# donut.net
KiCad netlist of a schematic drawn in EAGLE
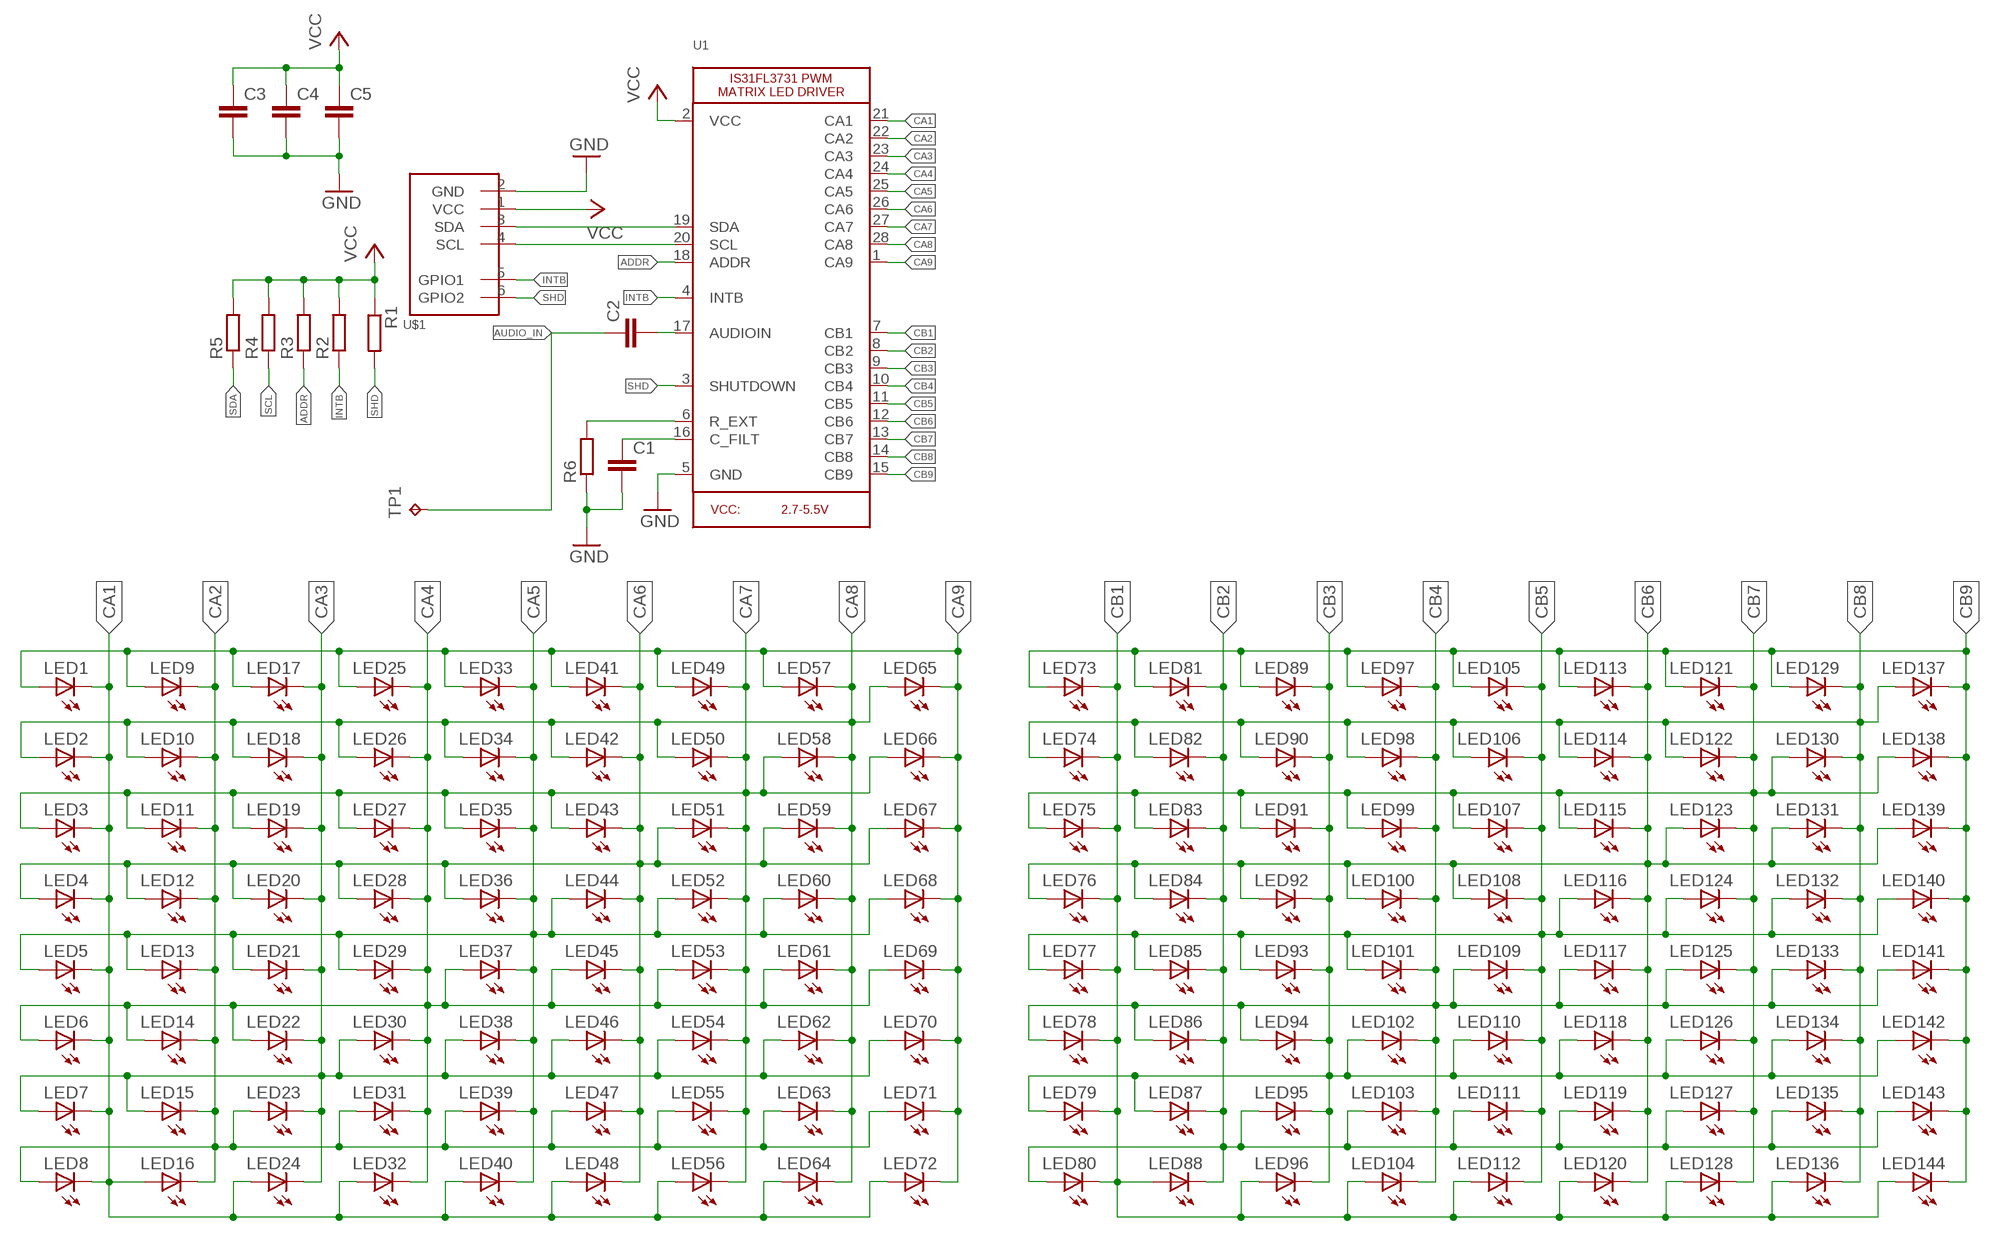
[diagram p0: schematic, sheet 1]

(export (version "E")
  (design (tool "Eeschema 10.0.6"))
  (components
    (comp (ref "C1")
      (value "C-EUC0603")
      (footprint "eagle-import:C0603")
      (libsource (lib "eagle-import") (part "C-EUC0603"))
    )
    (comp (ref "C2")
      (value "C-EUC0603")
      (footprint "eagle-import:C0603")
      (libsource (lib "eagle-import") (part "C-EUC0603"))
    )
    (comp (ref "C3")
      (value "C-EUC0603")
      (footprint "eagle-import:C0603")
      (libsource (lib "eagle-import") (part "C-EUC0603"))
    )
    (comp (ref "C4")
      (value "C-EUC0603")
      (footprint "eagle-import:C0603")
      (libsource (lib "eagle-import") (part "C-EUC0603"))
    )
    (comp (ref "C5")
      (value "C-EUC0603")
      (footprint "eagle-import:C0603")
      (libsource (lib "eagle-import") (part "C-EUC0603"))
    )
    (comp (ref "LED1")
      (value "LEDCHIP-LED0603")
      (footprint "eagle-import:CHIP-LED0603")
      (libsource (lib "eagle-import") (part "LEDCHIP-LED0603"))
    )
    (comp (ref "LED2")
      (value "LEDCHIP-LED0603")
      (footprint "eagle-import:CHIP-LED0603")
      (libsource (lib "eagle-import") (part "LEDCHIP-LED0603"))
    )
    (comp (ref "LED3")
      (value "LEDCHIP-LED0603")
      (footprint "eagle-import:CHIP-LED0603")
      (libsource (lib "eagle-import") (part "LEDCHIP-LED0603"))
    )
    (comp (ref "LED4")
      (value "LEDCHIP-LED0603")
      (footprint "eagle-import:CHIP-LED0603")
      (libsource (lib "eagle-import") (part "LEDCHIP-LED0603"))
    )
    (comp (ref "LED5")
      (value "LEDCHIP-LED0603")
      (footprint "eagle-import:CHIP-LED0603")
      (libsource (lib "eagle-import") (part "LEDCHIP-LED0603"))
    )
    (comp (ref "LED6")
      (value "LEDCHIP-LED0603")
      (footprint "eagle-import:CHIP-LED0603")
      (libsource (lib "eagle-import") (part "LEDCHIP-LED0603"))
    )
    (comp (ref "LED7")
      (value "LEDCHIP-LED0603")
      (footprint "eagle-import:CHIP-LED0603")
      (libsource (lib "eagle-import") (part "LEDCHIP-LED0603"))
    )
    (comp (ref "LED8")
      (value "LEDCHIP-LED0603")
      (footprint "eagle-import:CHIP-LED0603")
      (libsource (lib "eagle-import") (part "LEDCHIP-LED0603"))
    )
    (comp (ref "LED9")
      (value "LEDCHIP-LED0603")
      (footprint "eagle-import:CHIP-LED0603")
      (libsource (lib "eagle-import") (part "LEDCHIP-LED0603"))
    )
    (comp (ref "LED10")
      (value "LEDCHIP-LED0603")
      (footprint "eagle-import:CHIP-LED0603")
      (libsource (lib "eagle-import") (part "LEDCHIP-LED0603"))
    )
    (comp (ref "LED11")
      (value "LEDCHIP-LED0603")
      (footprint "eagle-import:CHIP-LED0603")
      (libsource (lib "eagle-import") (part "LEDCHIP-LED0603"))
    )
    (comp (ref "LED12")
      (value "LEDCHIP-LED0603")
      (footprint "eagle-import:CHIP-LED0603")
      (libsource (lib "eagle-import") (part "LEDCHIP-LED0603"))
    )
    (comp (ref "LED13")
      (value "LEDCHIP-LED0603")
      (footprint "eagle-import:CHIP-LED0603")
      (libsource (lib "eagle-import") (part "LEDCHIP-LED0603"))
    )
    (comp (ref "LED14")
      (value "LEDCHIP-LED0603")
      (footprint "eagle-import:CHIP-LED0603")
      (libsource (lib "eagle-import") (part "LEDCHIP-LED0603"))
    )
    (comp (ref "LED15")
      (value "LEDCHIP-LED0603")
      (footprint "eagle-import:CHIP-LED0603")
      (libsource (lib "eagle-import") (part "LEDCHIP-LED0603"))
    )
    (comp (ref "LED16")
      (value "LEDCHIP-LED0603")
      (footprint "eagle-import:CHIP-LED0603")
      (libsource (lib "eagle-import") (part "LEDCHIP-LED0603"))
    )
    (comp (ref "LED17")
      (value "LEDCHIP-LED0603")
      (footprint "eagle-import:CHIP-LED0603")
      (libsource (lib "eagle-import") (part "LEDCHIP-LED0603"))
    )
    (comp (ref "LED18")
      (value "LEDCHIP-LED0603")
      (footprint "eagle-import:CHIP-LED0603")
      (libsource (lib "eagle-import") (part "LEDCHIP-LED0603"))
    )
    (comp (ref "LED19")
      (value "LEDCHIP-LED0603")
      (footprint "eagle-import:CHIP-LED0603")
      (libsource (lib "eagle-import") (part "LEDCHIP-LED0603"))
    )
    (comp (ref "LED20")
      (value "LEDCHIP-LED0603")
      (footprint "eagle-import:CHIP-LED0603")
      (libsource (lib "eagle-import") (part "LEDCHIP-LED0603"))
    )
    (comp (ref "LED21")
      (value "LEDCHIP-LED0603")
      (footprint "eagle-import:CHIP-LED0603")
      (libsource (lib "eagle-import") (part "LEDCHIP-LED0603"))
    )
    (comp (ref "LED22")
      (value "LEDCHIP-LED0603")
      (footprint "eagle-import:CHIP-LED0603")
      (libsource (lib "eagle-import") (part "LEDCHIP-LED0603"))
    )
    (comp (ref "LED23")
      (value "LEDCHIP-LED0603")
      (footprint "eagle-import:CHIP-LED0603")
      (libsource (lib "eagle-import") (part "LEDCHIP-LED0603"))
    )
    (comp (ref "LED24")
      (value "LEDCHIP-LED0603")
      (footprint "eagle-import:CHIP-LED0603")
      (libsource (lib "eagle-import") (part "LEDCHIP-LED0603"))
    )
    (comp (ref "LED25")
      (value "LEDCHIP-LED0603")
      (footprint "eagle-import:CHIP-LED0603")
      (libsource (lib "eagle-import") (part "LEDCHIP-LED0603"))
    )
    (comp (ref "LED26")
      (value "LEDCHIP-LED0603")
      (footprint "eagle-import:CHIP-LED0603")
      (libsource (lib "eagle-import") (part "LEDCHIP-LED0603"))
    )
    (comp (ref "LED27")
      (value "LEDCHIP-LED0603")
      (footprint "eagle-import:CHIP-LED0603")
      (libsource (lib "eagle-import") (part "LEDCHIP-LED0603"))
    )
    (comp (ref "LED28")
      (value "LEDCHIP-LED0603")
      (footprint "eagle-import:CHIP-LED0603")
      (libsource (lib "eagle-import") (part "LEDCHIP-LED0603"))
    )
    (comp (ref "LED29")
      (value "LEDCHIP-LED0603")
      (footprint "eagle-import:CHIP-LED0603")
      (libsource (lib "eagle-import") (part "LEDCHIP-LED0603"))
    )
    (comp (ref "LED30")
      (value "LEDCHIP-LED0603")
      (footprint "eagle-import:CHIP-LED0603")
      (libsource (lib "eagle-import") (part "LEDCHIP-LED0603"))
    )
    (comp (ref "LED31")
      (value "LEDCHIP-LED0603")
      (footprint "eagle-import:CHIP-LED0603")
      (libsource (lib "eagle-import") (part "LEDCHIP-LED0603"))
    )
    (comp (ref "LED32")
      (value "LEDCHIP-LED0603")
      (footprint "eagle-import:CHIP-LED0603")
      (libsource (lib "eagle-import") (part "LEDCHIP-LED0603"))
    )
    (comp (ref "LED33")
      (value "LEDCHIP-LED0603")
      (footprint "eagle-import:CHIP-LED0603")
      (libsource (lib "eagle-import") (part "LEDCHIP-LED0603"))
    )
    (comp (ref "LED34")
      (value "LEDCHIP-LED0603")
      (footprint "eagle-import:CHIP-LED0603")
      (libsource (lib "eagle-import") (part "LEDCHIP-LED0603"))
    )
    (comp (ref "LED35")
      (value "LEDCHIP-LED0603")
      (footprint "eagle-import:CHIP-LED0603")
      (libsource (lib "eagle-import") (part "LEDCHIP-LED0603"))
    )
    (comp (ref "LED36")
      (value "LEDCHIP-LED0603")
      (footprint "eagle-import:CHIP-LED0603")
      (libsource (lib "eagle-import") (part "LEDCHIP-LED0603"))
    )
    (comp (ref "LED37")
      (value "LEDCHIP-LED0603")
      (footprint "eagle-import:CHIP-LED0603")
      (libsource (lib "eagle-import") (part "LEDCHIP-LED0603"))
    )
    (comp (ref "LED38")
      (value "LEDCHIP-LED0603")
      (footprint "eagle-import:CHIP-LED0603")
      (libsource (lib "eagle-import") (part "LEDCHIP-LED0603"))
    )
    (comp (ref "LED39")
      (value "LEDCHIP-LED0603")
      (footprint "eagle-import:CHIP-LED0603")
      (libsource (lib "eagle-import") (part "LEDCHIP-LED0603"))
    )
    (comp (ref "LED40")
      (value "LEDCHIP-LED0603")
      (footprint "eagle-import:CHIP-LED0603")
      (libsource (lib "eagle-import") (part "LEDCHIP-LED0603"))
    )
    (comp (ref "LED41")
      (value "LEDCHIP-LED0603")
      (footprint "eagle-import:CHIP-LED0603")
      (libsource (lib "eagle-import") (part "LEDCHIP-LED0603"))
    )
    (comp (ref "LED42")
      (value "LEDCHIP-LED0603")
      (footprint "eagle-import:CHIP-LED0603")
      (libsource (lib "eagle-import") (part "LEDCHIP-LED0603"))
    )
    (comp (ref "LED43")
      (value "LEDCHIP-LED0603")
      (footprint "eagle-import:CHIP-LED0603")
      (libsource (lib "eagle-import") (part "LEDCHIP-LED0603"))
    )
    (comp (ref "LED44")
      (value "LEDCHIP-LED0603")
      (footprint "eagle-import:CHIP-LED0603")
      (libsource (lib "eagle-import") (part "LEDCHIP-LED0603"))
    )
    (comp (ref "LED45")
      (value "LEDCHIP-LED0603")
      (footprint "eagle-import:CHIP-LED0603")
      (libsource (lib "eagle-import") (part "LEDCHIP-LED0603"))
    )
    (comp (ref "LED46")
      (value "LEDCHIP-LED0603")
      (footprint "eagle-import:CHIP-LED0603")
      (libsource (lib "eagle-import") (part "LEDCHIP-LED0603"))
    )
    (comp (ref "LED47")
      (value "LEDCHIP-LED0603")
      (footprint "eagle-import:CHIP-LED0603")
      (libsource (lib "eagle-import") (part "LEDCHIP-LED0603"))
    )
    (comp (ref "LED48")
      (value "LEDCHIP-LED0603")
      (footprint "eagle-import:CHIP-LED0603")
      (libsource (lib "eagle-import") (part "LEDCHIP-LED0603"))
    )
    (comp (ref "LED49")
      (value "LEDCHIP-LED0603")
      (footprint "eagle-import:CHIP-LED0603")
      (libsource (lib "eagle-import") (part "LEDCHIP-LED0603"))
    )
    (comp (ref "LED50")
      (value "LEDCHIP-LED0603")
      (footprint "eagle-import:CHIP-LED0603")
      (libsource (lib "eagle-import") (part "LEDCHIP-LED0603"))
    )
    (comp (ref "LED51")
      (value "LEDCHIP-LED0603")
      (footprint "eagle-import:CHIP-LED0603")
      (libsource (lib "eagle-import") (part "LEDCHIP-LED0603"))
    )
    (comp (ref "LED52")
      (value "LEDCHIP-LED0603")
      (footprint "eagle-import:CHIP-LED0603")
      (libsource (lib "eagle-import") (part "LEDCHIP-LED0603"))
    )
    (comp (ref "LED53")
      (value "LEDCHIP-LED0603")
      (footprint "eagle-import:CHIP-LED0603")
      (libsource (lib "eagle-import") (part "LEDCHIP-LED0603"))
    )
    (comp (ref "LED54")
      (value "LEDCHIP-LED0603")
      (footprint "eagle-import:CHIP-LED0603")
      (libsource (lib "eagle-import") (part "LEDCHIP-LED0603"))
    )
    (comp (ref "LED55")
      (value "LEDCHIP-LED0603")
      (footprint "eagle-import:CHIP-LED0603")
      (libsource (lib "eagle-import") (part "LEDCHIP-LED0603"))
    )
    (comp (ref "LED56")
      (value "LEDCHIP-LED0603")
      (footprint "eagle-import:CHIP-LED0603")
      (libsource (lib "eagle-import") (part "LEDCHIP-LED0603"))
    )
    (comp (ref "LED57")
      (value "LEDCHIP-LED0603")
      (footprint "eagle-import:CHIP-LED0603")
      (libsource (lib "eagle-import") (part "LEDCHIP-LED0603"))
    )
    (comp (ref "LED58")
      (value "LEDCHIP-LED0603")
      (footprint "eagle-import:CHIP-LED0603")
      (libsource (lib "eagle-import") (part "LEDCHIP-LED0603"))
    )
    (comp (ref "LED59")
      (value "LEDCHIP-LED0603")
      (footprint "eagle-import:CHIP-LED0603")
      (libsource (lib "eagle-import") (part "LEDCHIP-LED0603"))
    )
    (comp (ref "LED60")
      (value "LEDCHIP-LED0603")
      (footprint "eagle-import:CHIP-LED0603")
      (libsource (lib "eagle-import") (part "LEDCHIP-LED0603"))
    )
    (comp (ref "LED61")
      (value "LEDCHIP-LED0603")
      (footprint "eagle-import:CHIP-LED0603")
      (libsource (lib "eagle-import") (part "LEDCHIP-LED0603"))
    )
    (comp (ref "LED62")
      (value "LEDCHIP-LED0603")
      (footprint "eagle-import:CHIP-LED0603")
      (libsource (lib "eagle-import") (part "LEDCHIP-LED0603"))
    )
    (comp (ref "LED63")
      (value "LEDCHIP-LED0603")
      (footprint "eagle-import:CHIP-LED0603")
      (libsource (lib "eagle-import") (part "LEDCHIP-LED0603"))
    )
    (comp (ref "LED64")
      (value "LEDCHIP-LED0603")
      (footprint "eagle-import:CHIP-LED0603")
      (libsource (lib "eagle-import") (part "LEDCHIP-LED0603"))
    )
    (comp (ref "LED65")
      (value "LEDCHIP-LED0603")
      (footprint "eagle-import:CHIP-LED0603")
      (libsource (lib "eagle-import") (part "LEDCHIP-LED0603"))
    )
    (comp (ref "LED66")
      (value "LEDCHIP-LED0603")
      (footprint "eagle-import:CHIP-LED0603")
      (libsource (lib "eagle-import") (part "LEDCHIP-LED0603"))
    )
    (comp (ref "LED67")
      (value "LEDCHIP-LED0603")
      (footprint "eagle-import:CHIP-LED0603")
      (libsource (lib "eagle-import") (part "LEDCHIP-LED0603"))
    )
    (comp (ref "LED68")
      (value "LEDCHIP-LED0603")
      (footprint "eagle-import:CHIP-LED0603")
      (libsource (lib "eagle-import") (part "LEDCHIP-LED0603"))
    )
    (comp (ref "LED69")
      (value "LEDCHIP-LED0603")
      (footprint "eagle-import:CHIP-LED0603")
      (libsource (lib "eagle-import") (part "LEDCHIP-LED0603"))
    )
    (comp (ref "LED70")
      (value "LEDCHIP-LED0603")
      (footprint "eagle-import:CHIP-LED0603")
      (libsource (lib "eagle-import") (part "LEDCHIP-LED0603"))
    )
    (comp (ref "LED71")
      (value "LEDCHIP-LED0603")
      (footprint "eagle-import:CHIP-LED0603")
      (libsource (lib "eagle-import") (part "LEDCHIP-LED0603"))
    )
    (comp (ref "LED72")
      (value "LEDCHIP-LED0603")
      (footprint "eagle-import:CHIP-LED0603")
      (libsource (lib "eagle-import") (part "LEDCHIP-LED0603"))
    )
    (comp (ref "LED73")
      (value "LEDCHIP-LED0603")
      (footprint "eagle-import:CHIP-LED0603")
      (libsource (lib "eagle-import") (part "LEDCHIP-LED0603"))
    )
    (comp (ref "LED74")
      (value "LEDCHIP-LED0603")
      (footprint "eagle-import:CHIP-LED0603")
      (libsource (lib "eagle-import") (part "LEDCHIP-LED0603"))
    )
    (comp (ref "LED75")
      (value "LEDCHIP-LED0603")
      (footprint "eagle-import:CHIP-LED0603")
      (libsource (lib "eagle-import") (part "LEDCHIP-LED0603"))
    )
    (comp (ref "LED76")
      (value "LEDCHIP-LED0603")
      (footprint "eagle-import:CHIP-LED0603")
      (libsource (lib "eagle-import") (part "LEDCHIP-LED0603"))
    )
    (comp (ref "LED77")
      (value "LEDCHIP-LED0603")
      (footprint "eagle-import:CHIP-LED0603")
      (libsource (lib "eagle-import") (part "LEDCHIP-LED0603"))
    )
    (comp (ref "LED78")
      (value "LEDCHIP-LED0603")
      (footprint "eagle-import:CHIP-LED0603")
      (libsource (lib "eagle-import") (part "LEDCHIP-LED0603"))
    )
    (comp (ref "LED79")
      (value "LEDCHIP-LED0603")
      (footprint "eagle-import:CHIP-LED0603")
      (libsource (lib "eagle-import") (part "LEDCHIP-LED0603"))
    )
    (comp (ref "LED80")
      (value "LEDCHIP-LED0603")
      (footprint "eagle-import:CHIP-LED0603")
      (libsource (lib "eagle-import") (part "LEDCHIP-LED0603"))
    )
    (comp (ref "LED81")
      (value "LEDCHIP-LED0603")
      (footprint "eagle-import:CHIP-LED0603")
      (libsource (lib "eagle-import") (part "LEDCHIP-LED0603"))
    )
    (comp (ref "LED82")
      (value "LEDCHIP-LED0603")
      (footprint "eagle-import:CHIP-LED0603")
      (libsource (lib "eagle-import") (part "LEDCHIP-LED0603"))
    )
    (comp (ref "LED83")
      (value "LEDCHIP-LED0603")
      (footprint "eagle-import:CHIP-LED0603")
      (libsource (lib "eagle-import") (part "LEDCHIP-LED0603"))
    )
    (comp (ref "LED84")
      (value "LEDCHIP-LED0603")
      (footprint "eagle-import:CHIP-LED0603")
      (libsource (lib "eagle-import") (part "LEDCHIP-LED0603"))
    )
    (comp (ref "LED85")
      (value "LEDCHIP-LED0603")
      (footprint "eagle-import:CHIP-LED0603")
      (libsource (lib "eagle-import") (part "LEDCHIP-LED0603"))
    )
    (comp (ref "LED86")
      (value "LEDCHIP-LED0603")
      (footprint "eagle-import:CHIP-LED0603")
      (libsource (lib "eagle-import") (part "LEDCHIP-LED0603"))
    )
    (comp (ref "LED87")
      (value "LEDCHIP-LED0603")
      (footprint "eagle-import:CHIP-LED0603")
      (libsource (lib "eagle-import") (part "LEDCHIP-LED0603"))
    )
    (comp (ref "LED88")
      (value "LEDCHIP-LED0603")
      (footprint "eagle-import:CHIP-LED0603")
      (libsource (lib "eagle-import") (part "LEDCHIP-LED0603"))
    )
    (comp (ref "LED89")
      (value "LEDCHIP-LED0603")
      (footprint "eagle-import:CHIP-LED0603")
      (libsource (lib "eagle-import") (part "LEDCHIP-LED0603"))
    )
    (comp (ref "LED90")
      (value "LEDCHIP-LED0603")
      (footprint "eagle-import:CHIP-LED0603")
      (libsource (lib "eagle-import") (part "LEDCHIP-LED0603"))
    )
    (comp (ref "LED91")
      (value "LEDCHIP-LED0603")
      (footprint "eagle-import:CHIP-LED0603")
      (libsource (lib "eagle-import") (part "LEDCHIP-LED0603"))
    )
    (comp (ref "LED92")
      (value "LEDCHIP-LED0603")
      (footprint "eagle-import:CHIP-LED0603")
      (libsource (lib "eagle-import") (part "LEDCHIP-LED0603"))
    )
    (comp (ref "LED93")
      (value "LEDCHIP-LED0603")
      (footprint "eagle-import:CHIP-LED0603")
      (libsource (lib "eagle-import") (part "LEDCHIP-LED0603"))
    )
    (comp (ref "LED94")
      (value "LEDCHIP-LED0603")
      (footprint "eagle-import:CHIP-LED0603")
      (libsource (lib "eagle-import") (part "LEDCHIP-LED0603"))
    )
    (comp (ref "LED95")
      (value "LEDCHIP-LED0603")
      (footprint "eagle-import:CHIP-LED0603")
      (libsource (lib "eagle-import") (part "LEDCHIP-LED0603"))
    )
    (comp (ref "LED96")
      (value "LEDCHIP-LED0603")
      (footprint "eagle-import:CHIP-LED0603")
      (libsource (lib "eagle-import") (part "LEDCHIP-LED0603"))
    )
    (comp (ref "LED97")
      (value "LEDCHIP-LED0603")
      (footprint "eagle-import:CHIP-LED0603")
      (libsource (lib "eagle-import") (part "LEDCHIP-LED0603"))
    )
    (comp (ref "LED98")
      (value "LEDCHIP-LED0603")
      (footprint "eagle-import:CHIP-LED0603")
      (libsource (lib "eagle-import") (part "LEDCHIP-LED0603"))
    )
    (comp (ref "LED99")
      (value "LEDCHIP-LED0603")
      (footprint "eagle-import:CHIP-LED0603")
      (libsource (lib "eagle-import") (part "LEDCHIP-LED0603"))
    )
    (comp (ref "LED100")
      (value "LEDCHIP-LED0603")
      (footprint "eagle-import:CHIP-LED0603")
      (libsource (lib "eagle-import") (part "LEDCHIP-LED0603"))
    )
    (comp (ref "LED101")
      (value "LEDCHIP-LED0603")
      (footprint "eagle-import:CHIP-LED0603")
      (libsource (lib "eagle-import") (part "LEDCHIP-LED0603"))
    )
    (comp (ref "LED102")
      (value "LEDCHIP-LED0603")
      (footprint "eagle-import:CHIP-LED0603")
      (libsource (lib "eagle-import") (part "LEDCHIP-LED0603"))
    )
    (comp (ref "LED103")
      (value "LEDCHIP-LED0603")
      (footprint "eagle-import:CHIP-LED0603")
      (libsource (lib "eagle-import") (part "LEDCHIP-LED0603"))
    )
    (comp (ref "LED104")
      (value "LEDCHIP-LED0603")
      (footprint "eagle-import:CHIP-LED0603")
      (libsource (lib "eagle-import") (part "LEDCHIP-LED0603"))
    )
    (comp (ref "LED105")
      (value "LEDCHIP-LED0603")
      (footprint "eagle-import:CHIP-LED0603")
      (libsource (lib "eagle-import") (part "LEDCHIP-LED0603"))
    )
    (comp (ref "LED106")
      (value "LEDCHIP-LED0603")
      (footprint "eagle-import:CHIP-LED0603")
      (libsource (lib "eagle-import") (part "LEDCHIP-LED0603"))
    )
    (comp (ref "LED107")
      (value "LEDCHIP-LED0603")
      (footprint "eagle-import:CHIP-LED0603")
      (libsource (lib "eagle-import") (part "LEDCHIP-LED0603"))
    )
    (comp (ref "LED108")
      (value "LEDCHIP-LED0603")
      (footprint "eagle-import:CHIP-LED0603")
      (libsource (lib "eagle-import") (part "LEDCHIP-LED0603"))
    )
    (comp (ref "LED109")
      (value "LEDCHIP-LED0603")
      (footprint "eagle-import:CHIP-LED0603")
      (libsource (lib "eagle-import") (part "LEDCHIP-LED0603"))
    )
    (comp (ref "LED110")
      (value "LEDCHIP-LED0603")
      (footprint "eagle-import:CHIP-LED0603")
      (libsource (lib "eagle-import") (part "LEDCHIP-LED0603"))
    )
    (comp (ref "LED111")
      (value "LEDCHIP-LED0603")
      (footprint "eagle-import:CHIP-LED0603")
      (libsource (lib "eagle-import") (part "LEDCHIP-LED0603"))
    )
    (comp (ref "LED112")
      (value "LEDCHIP-LED0603")
      (footprint "eagle-import:CHIP-LED0603")
      (libsource (lib "eagle-import") (part "LEDCHIP-LED0603"))
    )
    (comp (ref "LED113")
      (value "LEDCHIP-LED0603")
      (footprint "eagle-import:CHIP-LED0603")
      (libsource (lib "eagle-import") (part "LEDCHIP-LED0603"))
    )
    (comp (ref "LED114")
      (value "LEDCHIP-LED0603")
      (footprint "eagle-import:CHIP-LED0603")
      (libsource (lib "eagle-import") (part "LEDCHIP-LED0603"))
    )
    (comp (ref "LED115")
      (value "LEDCHIP-LED0603")
      (footprint "eagle-import:CHIP-LED0603")
      (libsource (lib "eagle-import") (part "LEDCHIP-LED0603"))
    )
    (comp (ref "LED116")
      (value "LEDCHIP-LED0603")
      (footprint "eagle-import:CHIP-LED0603")
      (libsource (lib "eagle-import") (part "LEDCHIP-LED0603"))
    )
    (comp (ref "LED117")
      (value "LEDCHIP-LED0603")
      (footprint "eagle-import:CHIP-LED0603")
      (libsource (lib "eagle-import") (part "LEDCHIP-LED0603"))
    )
    (comp (ref "LED118")
      (value "LEDCHIP-LED0603")
      (footprint "eagle-import:CHIP-LED0603")
      (libsource (lib "eagle-import") (part "LEDCHIP-LED0603"))
    )
    (comp (ref "LED119")
      (value "LEDCHIP-LED0603")
      (footprint "eagle-import:CHIP-LED0603")
      (libsource (lib "eagle-import") (part "LEDCHIP-LED0603"))
    )
    (comp (ref "LED120")
      (value "LEDCHIP-LED0603")
      (footprint "eagle-import:CHIP-LED0603")
      (libsource (lib "eagle-import") (part "LEDCHIP-LED0603"))
    )
    (comp (ref "LED121")
      (value "LEDCHIP-LED0603")
      (footprint "eagle-import:CHIP-LED0603")
      (libsource (lib "eagle-import") (part "LEDCHIP-LED0603"))
    )
    (comp (ref "LED122")
      (value "LEDCHIP-LED0603")
      (footprint "eagle-import:CHIP-LED0603")
      (libsource (lib "eagle-import") (part "LEDCHIP-LED0603"))
    )
    (comp (ref "LED123")
      (value "LEDCHIP-LED0603")
      (footprint "eagle-import:CHIP-LED0603")
      (libsource (lib "eagle-import") (part "LEDCHIP-LED0603"))
    )
    (comp (ref "LED124")
      (value "LEDCHIP-LED0603")
      (footprint "eagle-import:CHIP-LED0603")
      (libsource (lib "eagle-import") (part "LEDCHIP-LED0603"))
    )
    (comp (ref "LED125")
      (value "LEDCHIP-LED0603")
      (footprint "eagle-import:CHIP-LED0603")
      (libsource (lib "eagle-import") (part "LEDCHIP-LED0603"))
    )
    (comp (ref "LED126")
      (value "LEDCHIP-LED0603")
      (footprint "eagle-import:CHIP-LED0603")
      (libsource (lib "eagle-import") (part "LEDCHIP-LED0603"))
    )
    (comp (ref "LED127")
      (value "LEDCHIP-LED0603")
      (footprint "eagle-import:CHIP-LED0603")
      (libsource (lib "eagle-import") (part "LEDCHIP-LED0603"))
    )
    (comp (ref "LED128")
      (value "LEDCHIP-LED0603")
      (footprint "eagle-import:CHIP-LED0603")
      (libsource (lib "eagle-import") (part "LEDCHIP-LED0603"))
    )
    (comp (ref "LED129")
      (value "LEDCHIP-LED0603")
      (footprint "eagle-import:CHIP-LED0603")
      (libsource (lib "eagle-import") (part "LEDCHIP-LED0603"))
    )
    (comp (ref "LED130")
      (value "LEDCHIP-LED0603")
      (footprint "eagle-import:CHIP-LED0603")
      (libsource (lib "eagle-import") (part "LEDCHIP-LED0603"))
    )
    (comp (ref "LED131")
      (value "LEDCHIP-LED0603")
      (footprint "eagle-import:CHIP-LED0603")
      (libsource (lib "eagle-import") (part "LEDCHIP-LED0603"))
    )
    (comp (ref "LED132")
      (value "LEDCHIP-LED0603")
      (footprint "eagle-import:CHIP-LED0603")
      (libsource (lib "eagle-import") (part "LEDCHIP-LED0603"))
    )
    (comp (ref "LED133")
      (value "LEDCHIP-LED0603")
      (footprint "eagle-import:CHIP-LED0603")
      (libsource (lib "eagle-import") (part "LEDCHIP-LED0603"))
    )
    (comp (ref "LED134")
      (value "LEDCHIP-LED0603")
      (footprint "eagle-import:CHIP-LED0603")
      (libsource (lib "eagle-import") (part "LEDCHIP-LED0603"))
    )
    (comp (ref "LED135")
      (value "LEDCHIP-LED0603")
      (footprint "eagle-import:CHIP-LED0603")
      (libsource (lib "eagle-import") (part "LEDCHIP-LED0603"))
    )
    (comp (ref "LED136")
      (value "LEDCHIP-LED0603")
      (footprint "eagle-import:CHIP-LED0603")
      (libsource (lib "eagle-import") (part "LEDCHIP-LED0603"))
    )
    (comp (ref "LED137")
      (value "LEDCHIP-LED0603")
      (footprint "eagle-import:CHIP-LED0603")
      (libsource (lib "eagle-import") (part "LEDCHIP-LED0603"))
    )
    (comp (ref "LED138")
      (value "LEDCHIP-LED0603")
      (footprint "eagle-import:CHIP-LED0603")
      (libsource (lib "eagle-import") (part "LEDCHIP-LED0603"))
    )
    (comp (ref "LED139")
      (value "LEDCHIP-LED0603")
      (footprint "eagle-import:CHIP-LED0603")
      (libsource (lib "eagle-import") (part "LEDCHIP-LED0603"))
    )
    (comp (ref "LED140")
      (value "LEDCHIP-LED0603")
      (footprint "eagle-import:CHIP-LED0603")
      (libsource (lib "eagle-import") (part "LEDCHIP-LED0603"))
    )
    (comp (ref "LED141")
      (value "LEDCHIP-LED0603")
      (footprint "eagle-import:CHIP-LED0603")
      (libsource (lib "eagle-import") (part "LEDCHIP-LED0603"))
    )
    (comp (ref "LED142")
      (value "LEDCHIP-LED0603")
      (footprint "eagle-import:CHIP-LED0603")
      (libsource (lib "eagle-import") (part "LEDCHIP-LED0603"))
    )
    (comp (ref "LED143")
      (value "LEDCHIP-LED0603")
      (footprint "eagle-import:CHIP-LED0603")
      (libsource (lib "eagle-import") (part "LEDCHIP-LED0603"))
    )
    (comp (ref "LED144")
      (value "LEDCHIP-LED0603")
      (footprint "eagle-import:CHIP-LED0603")
      (libsource (lib "eagle-import") (part "LEDCHIP-LED0603"))
    )
    (comp (ref "R1")
      (value "R-EU_R0603")
      (footprint "eagle-import:R0603")
      (libsource (lib "eagle-import") (part "R-EU_R0603"))
    )
    (comp (ref "R2")
      (value "R-EU_R0603")
      (footprint "eagle-import:R0603")
      (libsource (lib "eagle-import") (part "R-EU_R0603"))
    )
    (comp (ref "R3")
      (value "R-EU_R0603")
      (footprint "eagle-import:R0603")
      (libsource (lib "eagle-import") (part "R-EU_R0603"))
    )
    (comp (ref "R4")
      (value "R-EU_R0603")
      (footprint "eagle-import:R0603")
      (libsource (lib "eagle-import") (part "R-EU_R0603"))
    )
    (comp (ref "R5")
      (value "R-EU_R0603")
      (footprint "eagle-import:R0603")
      (libsource (lib "eagle-import") (part "R-EU_R0603"))
    )
    (comp (ref "R6")
      (value "R-EU_R0603")
      (footprint "eagle-import:R0603")
      (libsource (lib "eagle-import") (part "R-EU_R0603"))
    )
    (comp (ref "TP1")
      (value "TPB1,27")
      (footprint "eagle-import:B1,27")
      (libsource (lib "eagle-import") (part "TPB1,27"))
    )
    (comp (ref "U$1")
      (value "SAO-SHITTY-ADDONBADGE")
      (footprint "eagle-import:2X3-SHROUDED")
      (libsource (lib "eagle-import") (part "SAO-SHITTY-ADDONBADGE"))
    )
    (comp (ref "U1")
      (value "IS31FL3731SSOP")
      (footprint "eagle-import:SSOP28DB")
      (libsource (lib "eagle-import") (part "IS31FL3731SSOP"))
    )
  )
  (nets
    (net (code "1") (name "ADDR") (class "Default")
      (node (ref "R3") (pin "1") (pinfunction "1_1") (pintype "passive"))
      (node (ref "U1") (pin "18") (pinfunction "ADDR_18") (pintype "bidirectional"))
    )
    (net (code "2") (name "AUDIO_IN") (class "Default")
      (node (ref "C2") (pin "1") (pinfunction "1_1") (pintype "passive"))
      (node (ref "TP1") (pin "TP") (pinfunction "TP_TP") (pintype "input"))
    )
    (net (code "3") (name "CA1") (class "Default")
      (node (ref "LED1") (pin "C") (pinfunction "C_C") (pintype "passive"))
      (node (ref "LED16") (pin "A") (pinfunction "A_A") (pintype "passive"))
      (node (ref "LED2") (pin "C") (pinfunction "C_C") (pintype "passive"))
      (node (ref "LED24") (pin "A") (pinfunction "A_A") (pintype "passive"))
      (node (ref "LED3") (pin "C") (pinfunction "C_C") (pintype "passive"))
      (node (ref "LED32") (pin "A") (pinfunction "A_A") (pintype "passive"))
      (node (ref "LED4") (pin "C") (pinfunction "C_C") (pintype "passive"))
      (node (ref "LED40") (pin "A") (pinfunction "A_A") (pintype "passive"))
      (node (ref "LED48") (pin "A") (pinfunction "A_A") (pintype "passive"))
      (node (ref "LED5") (pin "C") (pinfunction "C_C") (pintype "passive"))
      (node (ref "LED56") (pin "A") (pinfunction "A_A") (pintype "passive"))
      (node (ref "LED6") (pin "C") (pinfunction "C_C") (pintype "passive"))
      (node (ref "LED64") (pin "A") (pinfunction "A_A") (pintype "passive"))
      (node (ref "LED7") (pin "C") (pinfunction "C_C") (pintype "passive"))
      (node (ref "LED72") (pin "A") (pinfunction "A_A") (pintype "passive"))
      (node (ref "LED8") (pin "C") (pinfunction "C_C") (pintype "passive"))
      (node (ref "U1") (pin "21") (pinfunction "CA1_21") (pintype "bidirectional"))
    )
    (net (code "4") (name "CA2") (class "Default")
      (node (ref "LED10") (pin "C") (pinfunction "C_C") (pintype "passive"))
      (node (ref "LED11") (pin "C") (pinfunction "C_C") (pintype "passive"))
      (node (ref "LED12") (pin "C") (pinfunction "C_C") (pintype "passive"))
      (node (ref "LED13") (pin "C") (pinfunction "C_C") (pintype "passive"))
      (node (ref "LED14") (pin "C") (pinfunction "C_C") (pintype "passive"))
      (node (ref "LED15") (pin "C") (pinfunction "C_C") (pintype "passive"))
      (node (ref "LED16") (pin "C") (pinfunction "C_C") (pintype "passive"))
      (node (ref "LED23") (pin "A") (pinfunction "A_A") (pintype "passive"))
      (node (ref "LED31") (pin "A") (pinfunction "A_A") (pintype "passive"))
      (node (ref "LED39") (pin "A") (pinfunction "A_A") (pintype "passive"))
      (node (ref "LED47") (pin "A") (pinfunction "A_A") (pintype "passive"))
      (node (ref "LED55") (pin "A") (pinfunction "A_A") (pintype "passive"))
      (node (ref "LED63") (pin "A") (pinfunction "A_A") (pintype "passive"))
      (node (ref "LED71") (pin "A") (pinfunction "A_A") (pintype "passive"))
      (node (ref "LED8") (pin "A") (pinfunction "A_A") (pintype "passive"))
      (node (ref "LED9") (pin "C") (pinfunction "C_C") (pintype "passive"))
      (node (ref "U1") (pin "22") (pinfunction "CA2_22") (pintype "bidirectional"))
    )
    (net (code "5") (name "CA3") (class "Default")
      (node (ref "LED15") (pin "A") (pinfunction "A_A") (pintype "passive"))
      (node (ref "LED17") (pin "C") (pinfunction "C_C") (pintype "passive"))
      (node (ref "LED18") (pin "C") (pinfunction "C_C") (pintype "passive"))
      (node (ref "LED19") (pin "C") (pinfunction "C_C") (pintype "passive"))
      (node (ref "LED20") (pin "C") (pinfunction "C_C") (pintype "passive"))
      (node (ref "LED21") (pin "C") (pinfunction "C_C") (pintype "passive"))
      (node (ref "LED22") (pin "C") (pinfunction "C_C") (pintype "passive"))
      (node (ref "LED23") (pin "C") (pinfunction "C_C") (pintype "passive"))
      (node (ref "LED24") (pin "C") (pinfunction "C_C") (pintype "passive"))
      (node (ref "LED30") (pin "A") (pinfunction "A_A") (pintype "passive"))
      (node (ref "LED38") (pin "A") (pinfunction "A_A") (pintype "passive"))
      (node (ref "LED46") (pin "A") (pinfunction "A_A") (pintype "passive"))
      (node (ref "LED54") (pin "A") (pinfunction "A_A") (pintype "passive"))
      (node (ref "LED62") (pin "A") (pinfunction "A_A") (pintype "passive"))
      (node (ref "LED7") (pin "A") (pinfunction "A_A") (pintype "passive"))
      (node (ref "LED70") (pin "A") (pinfunction "A_A") (pintype "passive"))
      (node (ref "U1") (pin "23") (pinfunction "CA3_23") (pintype "bidirectional"))
    )
    (net (code "6") (name "CA4") (class "Default")
      (node (ref "LED14") (pin "A") (pinfunction "A_A") (pintype "passive"))
      (node (ref "LED22") (pin "A") (pinfunction "A_A") (pintype "passive"))
      (node (ref "LED25") (pin "C") (pinfunction "C_C") (pintype "passive"))
      (node (ref "LED26") (pin "C") (pinfunction "C_C") (pintype "passive"))
      (node (ref "LED27") (pin "C") (pinfunction "C_C") (pintype "passive"))
      (node (ref "LED28") (pin "C") (pinfunction "C_C") (pintype "passive"))
      (node (ref "LED29") (pin "C") (pinfunction "C_C") (pintype "passive"))
      (node (ref "LED30") (pin "C") (pinfunction "C_C") (pintype "passive"))
      (node (ref "LED31") (pin "C") (pinfunction "C_C") (pintype "passive"))
      (node (ref "LED32") (pin "C") (pinfunction "C_C") (pintype "passive"))
      (node (ref "LED37") (pin "A") (pinfunction "A_A") (pintype "passive"))
      (node (ref "LED45") (pin "A") (pinfunction "A_A") (pintype "passive"))
      (node (ref "LED53") (pin "A") (pinfunction "A_A") (pintype "passive"))
      (node (ref "LED6") (pin "A") (pinfunction "A_A") (pintype "passive"))
      (node (ref "LED61") (pin "A") (pinfunction "A_A") (pintype "passive"))
      (node (ref "LED69") (pin "A") (pinfunction "A_A") (pintype "passive"))
      (node (ref "U1") (pin "24") (pinfunction "CA4_24") (pintype "bidirectional"))
    )
    (net (code "7") (name "CA5") (class "Default")
      (node (ref "LED13") (pin "A") (pinfunction "A_A") (pintype "passive"))
      (node (ref "LED21") (pin "A") (pinfunction "A_A") (pintype "passive"))
      (node (ref "LED29") (pin "A") (pinfunction "A_A") (pintype "passive"))
      (node (ref "LED33") (pin "C") (pinfunction "C_C") (pintype "passive"))
      (node (ref "LED34") (pin "C") (pinfunction "C_C") (pintype "passive"))
      (node (ref "LED35") (pin "C") (pinfunction "C_C") (pintype "passive"))
      (node (ref "LED36") (pin "C") (pinfunction "C_C") (pintype "passive"))
      (node (ref "LED37") (pin "C") (pinfunction "C_C") (pintype "passive"))
      (node (ref "LED38") (pin "C") (pinfunction "C_C") (pintype "passive"))
      (node (ref "LED39") (pin "C") (pinfunction "C_C") (pintype "passive"))
      (node (ref "LED40") (pin "C") (pinfunction "C_C") (pintype "passive"))
      (node (ref "LED44") (pin "A") (pinfunction "A_A") (pintype "passive"))
      (node (ref "LED5") (pin "A") (pinfunction "A_A") (pintype "passive"))
      (node (ref "LED52") (pin "A") (pinfunction "A_A") (pintype "passive"))
      (node (ref "LED60") (pin "A") (pinfunction "A_A") (pintype "passive"))
      (node (ref "LED68") (pin "A") (pinfunction "A_A") (pintype "passive"))
      (node (ref "U1") (pin "25") (pinfunction "CA5_25") (pintype "bidirectional"))
    )
    (net (code "8") (name "CA6") (class "Default")
      (node (ref "LED12") (pin "A") (pinfunction "A_A") (pintype "passive"))
      (node (ref "LED20") (pin "A") (pinfunction "A_A") (pintype "passive"))
      (node (ref "LED28") (pin "A") (pinfunction "A_A") (pintype "passive"))
      (node (ref "LED36") (pin "A") (pinfunction "A_A") (pintype "passive"))
      (node (ref "LED4") (pin "A") (pinfunction "A_A") (pintype "passive"))
      (node (ref "LED41") (pin "C") (pinfunction "C_C") (pintype "passive"))
      (node (ref "LED42") (pin "C") (pinfunction "C_C") (pintype "passive"))
      (node (ref "LED43") (pin "C") (pinfunction "C_C") (pintype "passive"))
      (node (ref "LED44") (pin "C") (pinfunction "C_C") (pintype "passive"))
      (node (ref "LED45") (pin "C") (pinfunction "C_C") (pintype "passive"))
      (node (ref "LED46") (pin "C") (pinfunction "C_C") (pintype "passive"))
      (node (ref "LED47") (pin "C") (pinfunction "C_C") (pintype "passive"))
      (node (ref "LED48") (pin "C") (pinfunction "C_C") (pintype "passive"))
      (node (ref "LED51") (pin "A") (pinfunction "A_A") (pintype "passive"))
      (node (ref "LED59") (pin "A") (pinfunction "A_A") (pintype "passive"))
      (node (ref "LED67") (pin "A") (pinfunction "A_A") (pintype "passive"))
      (node (ref "U1") (pin "26") (pinfunction "CA6_26") (pintype "bidirectional"))
    )
    (net (code "9") (name "CA7") (class "Default")
      (node (ref "LED11") (pin "A") (pinfunction "A_A") (pintype "passive"))
      (node (ref "LED19") (pin "A") (pinfunction "A_A") (pintype "passive"))
      (node (ref "LED27") (pin "A") (pinfunction "A_A") (pintype "passive"))
      (node (ref "LED3") (pin "A") (pinfunction "A_A") (pintype "passive"))
      (node (ref "LED35") (pin "A") (pinfunction "A_A") (pintype "passive"))
      (node (ref "LED43") (pin "A") (pinfunction "A_A") (pintype "passive"))
      (node (ref "LED49") (pin "C") (pinfunction "C_C") (pintype "passive"))
      (node (ref "LED50") (pin "C") (pinfunction "C_C") (pintype "passive"))
      (node (ref "LED51") (pin "C") (pinfunction "C_C") (pintype "passive"))
      (node (ref "LED52") (pin "C") (pinfunction "C_C") (pintype "passive"))
      (node (ref "LED53") (pin "C") (pinfunction "C_C") (pintype "passive"))
      (node (ref "LED54") (pin "C") (pinfunction "C_C") (pintype "passive"))
      (node (ref "LED55") (pin "C") (pinfunction "C_C") (pintype "passive"))
      (node (ref "LED56") (pin "C") (pinfunction "C_C") (pintype "passive"))
      (node (ref "LED58") (pin "A") (pinfunction "A_A") (pintype "passive"))
      (node (ref "LED66") (pin "A") (pinfunction "A_A") (pintype "passive"))
      (node (ref "U1") (pin "27") (pinfunction "CA7_27") (pintype "bidirectional"))
    )
    (net (code "10") (name "CA8") (class "Default")
      (node (ref "LED10") (pin "A") (pinfunction "A_A") (pintype "passive"))
      (node (ref "LED18") (pin "A") (pinfunction "A_A") (pintype "passive"))
      (node (ref "LED2") (pin "A") (pinfunction "A_A") (pintype "passive"))
      (node (ref "LED26") (pin "A") (pinfunction "A_A") (pintype "passive"))
      (node (ref "LED34") (pin "A") (pinfunction "A_A") (pintype "passive"))
      (node (ref "LED42") (pin "A") (pinfunction "A_A") (pintype "passive"))
      (node (ref "LED50") (pin "A") (pinfunction "A_A") (pintype "passive"))
      (node (ref "LED57") (pin "C") (pinfunction "C_C") (pintype "passive"))
      (node (ref "LED58") (pin "C") (pinfunction "C_C") (pintype "passive"))
      (node (ref "LED59") (pin "C") (pinfunction "C_C") (pintype "passive"))
      (node (ref "LED60") (pin "C") (pinfunction "C_C") (pintype "passive"))
      (node (ref "LED61") (pin "C") (pinfunction "C_C") (pintype "passive"))
      (node (ref "LED62") (pin "C") (pinfunction "C_C") (pintype "passive"))
      (node (ref "LED63") (pin "C") (pinfunction "C_C") (pintype "passive"))
      (node (ref "LED64") (pin "C") (pinfunction "C_C") (pintype "passive"))
      (node (ref "LED65") (pin "A") (pinfunction "A_A") (pintype "passive"))
      (node (ref "U1") (pin "28") (pinfunction "CA8_28") (pintype "bidirectional"))
    )
    (net (code "11") (name "CA9") (class "Default")
      (node (ref "LED1") (pin "A") (pinfunction "A_A") (pintype "passive"))
      (node (ref "LED17") (pin "A") (pinfunction "A_A") (pintype "passive"))
      (node (ref "LED25") (pin "A") (pinfunction "A_A") (pintype "passive"))
      (node (ref "LED33") (pin "A") (pinfunction "A_A") (pintype "passive"))
      (node (ref "LED41") (pin "A") (pinfunction "A_A") (pintype "passive"))
      (node (ref "LED49") (pin "A") (pinfunction "A_A") (pintype "passive"))
      (node (ref "LED57") (pin "A") (pinfunction "A_A") (pintype "passive"))
      (node (ref "LED65") (pin "C") (pinfunction "C_C") (pintype "passive"))
      (node (ref "LED66") (pin "C") (pinfunction "C_C") (pintype "passive"))
      (node (ref "LED67") (pin "C") (pinfunction "C_C") (pintype "passive"))
      (node (ref "LED68") (pin "C") (pinfunction "C_C") (pintype "passive"))
      (node (ref "LED69") (pin "C") (pinfunction "C_C") (pintype "passive"))
      (node (ref "LED70") (pin "C") (pinfunction "C_C") (pintype "passive"))
      (node (ref "LED71") (pin "C") (pinfunction "C_C") (pintype "passive"))
      (node (ref "LED72") (pin "C") (pinfunction "C_C") (pintype "passive"))
      (node (ref "LED9") (pin "A") (pinfunction "A_A") (pintype "passive"))
      (node (ref "U1") (pin "1") (pinfunction "CA9_1") (pintype "bidirectional"))
    )
    (net (code "12") (name "CB1") (class "Default")
      (node (ref "LED104") (pin "A") (pinfunction "A_A") (pintype "passive"))
      (node (ref "LED112") (pin "A") (pinfunction "A_A") (pintype "passive"))
      (node (ref "LED120") (pin "A") (pinfunction "A_A") (pintype "passive"))
      (node (ref "LED128") (pin "A") (pinfunction "A_A") (pintype "passive"))
      (node (ref "LED136") (pin "A") (pinfunction "A_A") (pintype "passive"))
      (node (ref "LED144") (pin "A") (pinfunction "A_A") (pintype "passive"))
      (node (ref "LED73") (pin "C") (pinfunction "C_C") (pintype "passive"))
      (node (ref "LED74") (pin "C") (pinfunction "C_C") (pintype "passive"))
      (node (ref "LED75") (pin "C") (pinfunction "C_C") (pintype "passive"))
      (node (ref "LED76") (pin "C") (pinfunction "C_C") (pintype "passive"))
      (node (ref "LED77") (pin "C") (pinfunction "C_C") (pintype "passive"))
      (node (ref "LED78") (pin "C") (pinfunction "C_C") (pintype "passive"))
      (node (ref "LED79") (pin "C") (pinfunction "C_C") (pintype "passive"))
      (node (ref "LED80") (pin "C") (pinfunction "C_C") (pintype "passive"))
      (node (ref "LED88") (pin "A") (pinfunction "A_A") (pintype "passive"))
      (node (ref "LED96") (pin "A") (pinfunction "A_A") (pintype "passive"))
      (node (ref "U1") (pin "7") (pinfunction "CB1_7") (pintype "bidirectional"))
    )
    (net (code "13") (name "CB2") (class "Default")
      (node (ref "LED103") (pin "A") (pinfunction "A_A") (pintype "passive"))
      (node (ref "LED111") (pin "A") (pinfunction "A_A") (pintype "passive"))
      (node (ref "LED119") (pin "A") (pinfunction "A_A") (pintype "passive"))
      (node (ref "LED127") (pin "A") (pinfunction "A_A") (pintype "passive"))
      (node (ref "LED135") (pin "A") (pinfunction "A_A") (pintype "passive"))
      (node (ref "LED143") (pin "A") (pinfunction "A_A") (pintype "passive"))
      (node (ref "LED80") (pin "A") (pinfunction "A_A") (pintype "passive"))
      (node (ref "LED81") (pin "C") (pinfunction "C_C") (pintype "passive"))
      (node (ref "LED82") (pin "C") (pinfunction "C_C") (pintype "passive"))
      (node (ref "LED83") (pin "C") (pinfunction "C_C") (pintype "passive"))
      (node (ref "LED84") (pin "C") (pinfunction "C_C") (pintype "passive"))
      (node (ref "LED85") (pin "C") (pinfunction "C_C") (pintype "passive"))
      (node (ref "LED86") (pin "C") (pinfunction "C_C") (pintype "passive"))
      (node (ref "LED87") (pin "C") (pinfunction "C_C") (pintype "passive"))
      (node (ref "LED88") (pin "C") (pinfunction "C_C") (pintype "passive"))
      (node (ref "LED95") (pin "A") (pinfunction "A_A") (pintype "passive"))
      (node (ref "U1") (pin "8") (pinfunction "CB2_8") (pintype "bidirectional"))
    )
    (net (code "14") (name "CB3") (class "Default")
      (node (ref "LED102") (pin "A") (pinfunction "A_A") (pintype "passive"))
      (node (ref "LED110") (pin "A") (pinfunction "A_A") (pintype "passive"))
      (node (ref "LED118") (pin "A") (pinfunction "A_A") (pintype "passive"))
      (node (ref "LED126") (pin "A") (pinfunction "A_A") (pintype "passive"))
      (node (ref "LED134") (pin "A") (pinfunction "A_A") (pintype "passive"))
      (node (ref "LED142") (pin "A") (pinfunction "A_A") (pintype "passive"))
      (node (ref "LED79") (pin "A") (pinfunction "A_A") (pintype "passive"))
      (node (ref "LED87") (pin "A") (pinfunction "A_A") (pintype "passive"))
      (node (ref "LED89") (pin "C") (pinfunction "C_C") (pintype "passive"))
      (node (ref "LED90") (pin "C") (pinfunction "C_C") (pintype "passive"))
      (node (ref "LED91") (pin "C") (pinfunction "C_C") (pintype "passive"))
      (node (ref "LED92") (pin "C") (pinfunction "C_C") (pintype "passive"))
      (node (ref "LED93") (pin "C") (pinfunction "C_C") (pintype "passive"))
      (node (ref "LED94") (pin "C") (pinfunction "C_C") (pintype "passive"))
      (node (ref "LED95") (pin "C") (pinfunction "C_C") (pintype "passive"))
      (node (ref "LED96") (pin "C") (pinfunction "C_C") (pintype "passive"))
      (node (ref "U1") (pin "9") (pinfunction "CB3_9") (pintype "bidirectional"))
    )
    (net (code "15") (name "CB4") (class "Default")
      (node (ref "LED100") (pin "C") (pinfunction "C_C") (pintype "passive"))
      (node (ref "LED101") (pin "C") (pinfunction "C_C") (pintype "passive"))
      (node (ref "LED102") (pin "C") (pinfunction "C_C") (pintype "passive"))
      (node (ref "LED103") (pin "C") (pinfunction "C_C") (pintype "passive"))
      (node (ref "LED104") (pin "C") (pinfunction "C_C") (pintype "passive"))
      (node (ref "LED109") (pin "A") (pinfunction "A_A") (pintype "passive"))
      (node (ref "LED117") (pin "A") (pinfunction "A_A") (pintype "passive"))
      (node (ref "LED125") (pin "A") (pinfunction "A_A") (pintype "passive"))
      (node (ref "LED133") (pin "A") (pinfunction "A_A") (pintype "passive"))
      (node (ref "LED141") (pin "A") (pinfunction "A_A") (pintype "passive"))
      (node (ref "LED78") (pin "A") (pinfunction "A_A") (pintype "passive"))
      (node (ref "LED86") (pin "A") (pinfunction "A_A") (pintype "passive"))
      (node (ref "LED94") (pin "A") (pinfunction "A_A") (pintype "passive"))
      (node (ref "LED97") (pin "C") (pinfunction "C_C") (pintype "passive"))
      (node (ref "LED98") (pin "C") (pinfunction "C_C") (pintype "passive"))
      (node (ref "LED99") (pin "C") (pinfunction "C_C") (pintype "passive"))
      (node (ref "U1") (pin "10") (pinfunction "CB4_10") (pintype "bidirectional"))
    )
    (net (code "16") (name "CB5") (class "Default")
      (node (ref "LED101") (pin "A") (pinfunction "A_A") (pintype "passive"))
      (node (ref "LED105") (pin "C") (pinfunction "C_C") (pintype "passive"))
      (node (ref "LED106") (pin "C") (pinfunction "C_C") (pintype "passive"))
      (node (ref "LED107") (pin "C") (pinfunction "C_C") (pintype "passive"))
      (node (ref "LED108") (pin "C") (pinfunction "C_C") (pintype "passive"))
      (node (ref "LED109") (pin "C") (pinfunction "C_C") (pintype "passive"))
      (node (ref "LED110") (pin "C") (pinfunction "C_C") (pintype "passive"))
      (node (ref "LED111") (pin "C") (pinfunction "C_C") (pintype "passive"))
      (node (ref "LED112") (pin "C") (pinfunction "C_C") (pintype "passive"))
      (node (ref "LED116") (pin "A") (pinfunction "A_A") (pintype "passive"))
      (node (ref "LED124") (pin "A") (pinfunction "A_A") (pintype "passive"))
      (node (ref "LED132") (pin "A") (pinfunction "A_A") (pintype "passive"))
      (node (ref "LED140") (pin "A") (pinfunction "A_A") (pintype "passive"))
      (node (ref "LED77") (pin "A") (pinfunction "A_A") (pintype "passive"))
      (node (ref "LED85") (pin "A") (pinfunction "A_A") (pintype "passive"))
      (node (ref "LED93") (pin "A") (pinfunction "A_A") (pintype "passive"))
      (node (ref "U1") (pin "11") (pinfunction "CB5_11") (pintype "bidirectional"))
    )
    (net (code "17") (name "CB6") (class "Default")
      (node (ref "LED100") (pin "A") (pinfunction "A_A") (pintype "passive"))
      (node (ref "LED108") (pin "A") (pinfunction "A_A") (pintype "passive"))
      (node (ref "LED113") (pin "C") (pinfunction "C_C") (pintype "passive"))
      (node (ref "LED114") (pin "C") (pinfunction "C_C") (pintype "passive"))
      (node (ref "LED115") (pin "C") (pinfunction "C_C") (pintype "passive"))
      (node (ref "LED116") (pin "C") (pinfunction "C_C") (pintype "passive"))
      (node (ref "LED117") (pin "C") (pinfunction "C_C") (pintype "passive"))
      (node (ref "LED118") (pin "C") (pinfunction "C_C") (pintype "passive"))
      (node (ref "LED119") (pin "C") (pinfunction "C_C") (pintype "passive"))
      (node (ref "LED120") (pin "C") (pinfunction "C_C") (pintype "passive"))
      (node (ref "LED123") (pin "A") (pinfunction "A_A") (pintype "passive"))
      (node (ref "LED131") (pin "A") (pinfunction "A_A") (pintype "passive"))
      (node (ref "LED139") (pin "A") (pinfunction "A_A") (pintype "passive"))
      (node (ref "LED76") (pin "A") (pinfunction "A_A") (pintype "passive"))
      (node (ref "LED84") (pin "A") (pinfunction "A_A") (pintype "passive"))
      (node (ref "LED92") (pin "A") (pinfunction "A_A") (pintype "passive"))
      (node (ref "U1") (pin "12") (pinfunction "CB6_12") (pintype "bidirectional"))
    )
    (net (code "18") (name "CB7") (class "Default")
      (node (ref "LED107") (pin "A") (pinfunction "A_A") (pintype "passive"))
      (node (ref "LED115") (pin "A") (pinfunction "A_A") (pintype "passive"))
      (node (ref "LED121") (pin "C") (pinfunction "C_C") (pintype "passive"))
      (node (ref "LED122") (pin "C") (pinfunction "C_C") (pintype "passive"))
      (node (ref "LED123") (pin "C") (pinfunction "C_C") (pintype "passive"))
      (node (ref "LED124") (pin "C") (pinfunction "C_C") (pintype "passive"))
      (node (ref "LED125") (pin "C") (pinfunction "C_C") (pintype "passive"))
      (node (ref "LED126") (pin "C") (pinfunction "C_C") (pintype "passive"))
      (node (ref "LED127") (pin "C") (pinfunction "C_C") (pintype "passive"))
      (node (ref "LED128") (pin "C") (pinfunction "C_C") (pintype "passive"))
      (node (ref "LED130") (pin "A") (pinfunction "A_A") (pintype "passive"))
      (node (ref "LED138") (pin "A") (pinfunction "A_A") (pintype "passive"))
      (node (ref "LED75") (pin "A") (pinfunction "A_A") (pintype "passive"))
      (node (ref "LED83") (pin "A") (pinfunction "A_A") (pintype "passive"))
      (node (ref "LED91") (pin "A") (pinfunction "A_A") (pintype "passive"))
      (node (ref "LED99") (pin "A") (pinfunction "A_A") (pintype "passive"))
      (node (ref "U1") (pin "13") (pinfunction "CB7_13") (pintype "bidirectional"))
    )
    (net (code "19") (name "CB8") (class "Default")
      (node (ref "LED106") (pin "A") (pinfunction "A_A") (pintype "passive"))
      (node (ref "LED114") (pin "A") (pinfunction "A_A") (pintype "passive"))
      (node (ref "LED122") (pin "A") (pinfunction "A_A") (pintype "passive"))
      (node (ref "LED129") (pin "C") (pinfunction "C_C") (pintype "passive"))
      (node (ref "LED130") (pin "C") (pinfunction "C_C") (pintype "passive"))
      (node (ref "LED131") (pin "C") (pinfunction "C_C") (pintype "passive"))
      (node (ref "LED132") (pin "C") (pinfunction "C_C") (pintype "passive"))
      (node (ref "LED133") (pin "C") (pinfunction "C_C") (pintype "passive"))
      (node (ref "LED134") (pin "C") (pinfunction "C_C") (pintype "passive"))
      (node (ref "LED135") (pin "C") (pinfunction "C_C") (pintype "passive"))
      (node (ref "LED136") (pin "C") (pinfunction "C_C") (pintype "passive"))
      (node (ref "LED137") (pin "A") (pinfunction "A_A") (pintype "passive"))
      (node (ref "LED74") (pin "A") (pinfunction "A_A") (pintype "passive"))
      (node (ref "LED82") (pin "A") (pinfunction "A_A") (pintype "passive"))
      (node (ref "LED90") (pin "A") (pinfunction "A_A") (pintype "passive"))
      (node (ref "LED98") (pin "A") (pinfunction "A_A") (pintype "passive"))
      (node (ref "U1") (pin "14") (pinfunction "CB8_14") (pintype "bidirectional"))
    )
    (net (code "20") (name "CB9") (class "Default")
      (node (ref "LED105") (pin "A") (pinfunction "A_A") (pintype "passive"))
      (node (ref "LED113") (pin "A") (pinfunction "A_A") (pintype "passive"))
      (node (ref "LED121") (pin "A") (pinfunction "A_A") (pintype "passive"))
      (node (ref "LED129") (pin "A") (pinfunction "A_A") (pintype "passive"))
      (node (ref "LED137") (pin "C") (pinfunction "C_C") (pintype "passive"))
      (node (ref "LED138") (pin "C") (pinfunction "C_C") (pintype "passive"))
      (node (ref "LED139") (pin "C") (pinfunction "C_C") (pintype "passive"))
      (node (ref "LED140") (pin "C") (pinfunction "C_C") (pintype "passive"))
      (node (ref "LED141") (pin "C") (pinfunction "C_C") (pintype "passive"))
      (node (ref "LED142") (pin "C") (pinfunction "C_C") (pintype "passive"))
      (node (ref "LED143") (pin "C") (pinfunction "C_C") (pintype "passive"))
      (node (ref "LED144") (pin "C") (pinfunction "C_C") (pintype "passive"))
      (node (ref "LED73") (pin "A") (pinfunction "A_A") (pintype "passive"))
      (node (ref "LED81") (pin "A") (pinfunction "A_A") (pintype "passive"))
      (node (ref "LED89") (pin "A") (pinfunction "A_A") (pintype "passive"))
      (node (ref "LED97") (pin "A") (pinfunction "A_A") (pintype "passive"))
      (node (ref "U1") (pin "15") (pinfunction "CB9_15") (pintype "bidirectional"))
    )
    (net (code "21") (name "GND") (class "Default")
      (node (ref "C1") (pin "2") (pinfunction "2_2") (pintype "passive"))
      (node (ref "C3") (pin "2") (pinfunction "2_2") (pintype "passive"))
      (node (ref "C4") (pin "2") (pinfunction "2_2") (pintype "passive"))
      (node (ref "C5") (pin "2") (pinfunction "2_2") (pintype "passive"))
      (node (ref "R6") (pin "1") (pinfunction "1_1") (pintype "passive"))
      (node (ref "U$1") (pin "2") (pinfunction "GND_2") (pintype "bidirectional"))
      (node (ref "U1") (pin "5") (pinfunction "GND_5") (pintype "power_in"))
    )
    (net (code "22") (name "INTB") (class "Default")
      (node (ref "R2") (pin "1") (pinfunction "1_1") (pintype "passive"))
      (node (ref "U$1") (pin "5") (pinfunction "GPIO1_5") (pintype "bidirectional"))
      (node (ref "U1") (pin "4") (pinfunction "INTB_4") (pintype "output"))
    )
    (net (code "23") (name "Net-(U1-AUDIOIN)") (class "Default")
      (node (ref "C2") (pin "2") (pinfunction "2_2") (pintype "passive"))
      (node (ref "U1") (pin "17") (pinfunction "AUDIOIN_17") (pintype "input"))
    )
    (net (code "24") (name "Net-(U1-C_FILT)") (class "Default")
      (node (ref "C1") (pin "1") (pinfunction "1_1") (pintype "passive"))
      (node (ref "U1") (pin "16") (pinfunction "C_FILT_16") (pintype "bidirectional"))
    )
    (net (code "25") (name "Net-(U1-R_EXT)") (class "Default")
      (node (ref "R6") (pin "2") (pinfunction "2_2") (pintype "passive"))
      (node (ref "U1") (pin "6") (pinfunction "R_EXT_6") (pintype "bidirectional"))
    )
    (net (code "26") (name "SCL") (class "Default")
      (node (ref "R4") (pin "1") (pinfunction "1_1") (pintype "passive"))
      (node (ref "U$1") (pin "4") (pinfunction "SCL_4") (pintype "bidirectional"))
      (node (ref "U1") (pin "20") (pinfunction "SCL_20") (pintype "bidirectional"))
    )
    (net (code "27") (name "SDA") (class "Default")
      (node (ref "R5") (pin "1") (pinfunction "1_1") (pintype "passive"))
      (node (ref "U$1") (pin "3") (pinfunction "SDA_3") (pintype "bidirectional"))
      (node (ref "U1") (pin "19") (pinfunction "SDA_19") (pintype "bidirectional"))
    )
    (net (code "28") (name "SHD") (class "Default")
      (node (ref "R1") (pin "2") (pinfunction "2_2") (pintype "passive"))
      (node (ref "U$1") (pin "6") (pinfunction "GPIO2_6") (pintype "bidirectional"))
      (node (ref "U1") (pin "3") (pinfunction "SHUTDOWN_3") (pintype "input"))
    )
    (net (code "29") (name "VCC") (class "Default")
      (node (ref "C3") (pin "1") (pinfunction "1_1") (pintype "passive"))
      (node (ref "C4") (pin "1") (pinfunction "1_1") (pintype "passive"))
      (node (ref "C5") (pin "1") (pinfunction "1_1") (pintype "passive"))
      (node (ref "R1") (pin "1") (pinfunction "1_1") (pintype "passive"))
      (node (ref "R2") (pin "2") (pinfunction "2_2") (pintype "passive"))
      (node (ref "R3") (pin "2") (pinfunction "2_2") (pintype "passive"))
      (node (ref "R4") (pin "2") (pinfunction "2_2") (pintype "passive"))
      (node (ref "R5") (pin "2") (pinfunction "2_2") (pintype "passive"))
      (node (ref "U$1") (pin "1") (pinfunction "VCC_1") (pintype "bidirectional"))
      (node (ref "U1") (pin "2") (pinfunction "VCC_2") (pintype "power_in"))
    )
  )
)
